# 6_MCU_Control_Connecter.net
KiCad netlist of a schematic drawn in Altium Designer
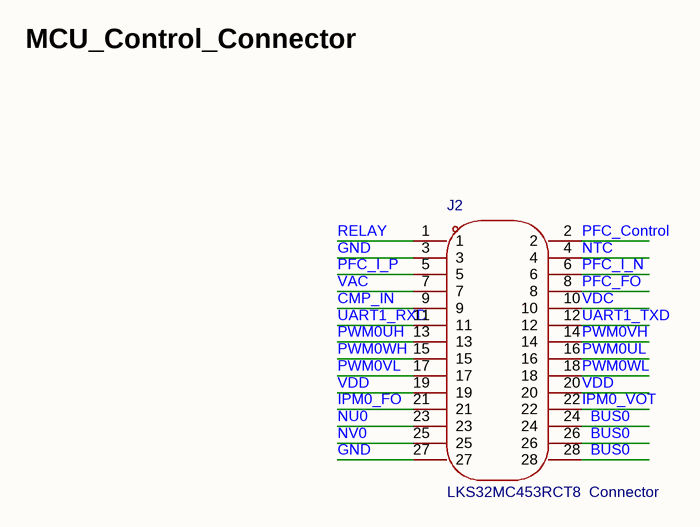
[diagram p0: 6_MCU_Control_Connecter.schdoc]

(export (version "E")
  (design (tool "Eeschema 10.0.6"))
  (components
    (comp (ref "J2")
      (value "LKS32MC453RCT8  Connector")
      (footprint "HDR-TH_28P-P2.54-V-F-R2-C14-S2.54-1")
      (fields (field (name "MANUFACTURER") "CONNFLY"))
      (libsource (lib "altium-import") (part "root_0_DS1023-2*14SF11_"))
    )
  )
  (nets
    (net (code "1") (name "/BUS0") (class "Default")
      (node (ref "J2") (pin "24") (pinfunction "24_24") (pintype "passive"))
      (node (ref "J2") (pin "26") (pinfunction "26_26") (pintype "passive"))
      (node (ref "J2") (pin "28") (pinfunction "28_28") (pintype "passive"))
    )
    (net (code "2") (name "/CMP_IN") (class "Default")
      (node (ref "J2") (pin "9") (pinfunction "9_9") (pintype "passive"))
    )
    (net (code "3") (name "/GND") (class "Default")
      (node (ref "J2") (pin "27") (pinfunction "27_27") (pintype "passive"))
      (node (ref "J2") (pin "3") (pinfunction "3_3") (pintype "passive"))
    )
    (net (code "4") (name "/IPM0_FO") (class "Default")
      (node (ref "J2") (pin "21") (pinfunction "21_21") (pintype "passive"))
    )
    (net (code "5") (name "/IPM0_VOT") (class "Default")
      (node (ref "J2") (pin "22") (pinfunction "22_22") (pintype "passive"))
    )
    (net (code "6") (name "/NTC") (class "Default")
      (node (ref "J2") (pin "4") (pinfunction "4_4") (pintype "passive"))
    )
    (net (code "7") (name "/NU0") (class "Default")
      (node (ref "J2") (pin "23") (pinfunction "23_23") (pintype "passive"))
    )
    (net (code "8") (name "/NV0") (class "Default")
      (node (ref "J2") (pin "25") (pinfunction "25_25") (pintype "passive"))
    )
    (net (code "9") (name "/PFC_Control") (class "Default")
      (node (ref "J2") (pin "2") (pinfunction "2_2") (pintype "passive"))
    )
    (net (code "10") (name "/PFC_FO") (class "Default")
      (node (ref "J2") (pin "8") (pinfunction "8_8") (pintype "passive"))
    )
    (net (code "11") (name "/PFC_I_N") (class "Default")
      (node (ref "J2") (pin "6") (pinfunction "6_6") (pintype "passive"))
    )
    (net (code "12") (name "/PFC_I_P") (class "Default")
      (node (ref "J2") (pin "5") (pinfunction "5_5") (pintype "passive"))
    )
    (net (code "13") (name "/PWM0UH") (class "Default")
      (node (ref "J2") (pin "13") (pinfunction "13_13") (pintype "passive"))
    )
    (net (code "14") (name "/PWM0UL") (class "Default")
      (node (ref "J2") (pin "16") (pinfunction "16_16") (pintype "passive"))
    )
    (net (code "15") (name "/PWM0VH") (class "Default")
      (node (ref "J2") (pin "14") (pinfunction "14_14") (pintype "passive"))
    )
    (net (code "16") (name "/PWM0VL") (class "Default")
      (node (ref "J2") (pin "17") (pinfunction "17_17") (pintype "passive"))
    )
    (net (code "17") (name "/PWM0WH") (class "Default")
      (node (ref "J2") (pin "15") (pinfunction "15_15") (pintype "passive"))
    )
    (net (code "18") (name "/PWM0WL") (class "Default")
      (node (ref "J2") (pin "18") (pinfunction "18_18") (pintype "passive"))
    )
    (net (code "19") (name "/RELAY") (class "Default")
      (node (ref "J2") (pin "1") (pinfunction "1_1") (pintype "passive"))
    )
    (net (code "20") (name "/UART1_RXD") (class "Default")
      (node (ref "J2") (pin "11") (pinfunction "11_11") (pintype "passive"))
    )
    (net (code "21") (name "/UART1_TXD") (class "Default")
      (node (ref "J2") (pin "12") (pinfunction "12_12") (pintype "passive"))
    )
    (net (code "22") (name "/VAC") (class "Default")
      (node (ref "J2") (pin "7") (pinfunction "7_7") (pintype "passive"))
    )
    (net (code "23") (name "/VDC") (class "Default")
      (node (ref "J2") (pin "10") (pinfunction "10_10") (pintype "passive"))
    )
    (net (code "24") (name "/VDD") (class "Default")
      (node (ref "J2") (pin "19") (pinfunction "19_19") (pintype "passive"))
      (node (ref "J2") (pin "20") (pinfunction "20_20") (pintype "passive"))
    )
  )
)
